# HDMI.net
KiCad netlist of a schematic drawn in Altium Designer
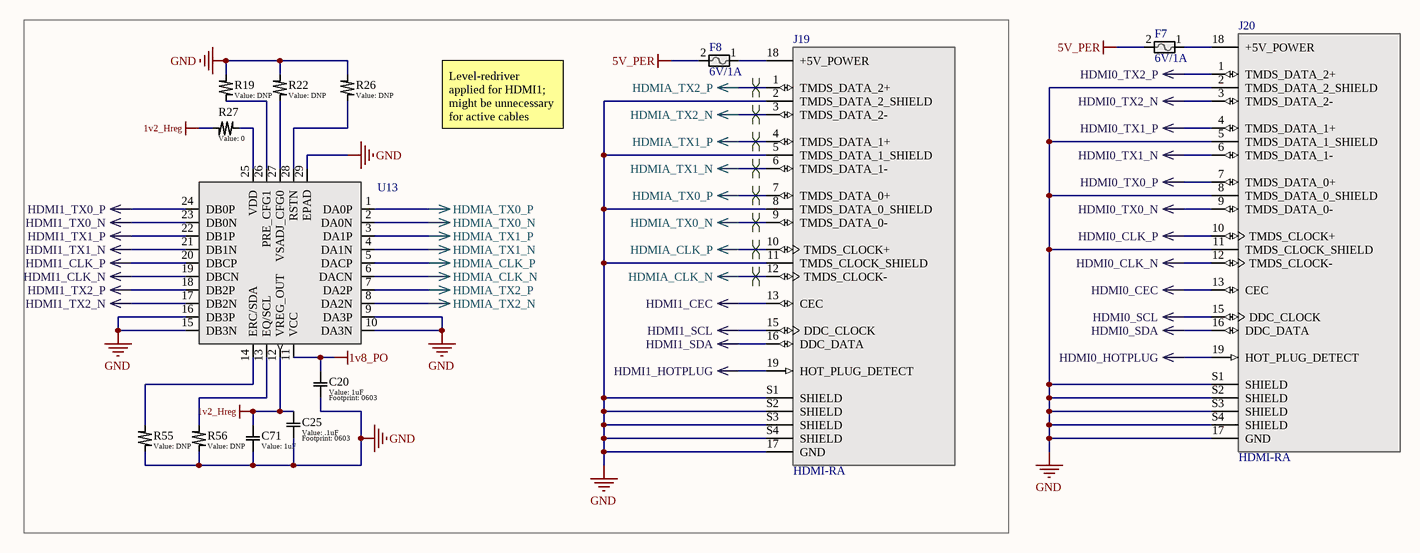
[diagram p0: HDMI.SchDoc]

(export (version "E")
  (design (tool "Eeschema 10.0.6"))
  (components
    (comp (ref "C20")
      (value "1uF")
      (footprint "0603")
      (fields
        (field (name "VOLTAGE") ">10V")
        (field (name "TOLERANCE") "10%")
        (field (name "Comment") "Generic Capacitor")
      )
      (libsource (lib "Capacitors") (part "Generic Capacitor"))
    )
    (comp (ref "C25")
      (value ".1uF")
      (footprint "0603")
      (fields
        (field (name "VOLTAGE") ">10V")
        (field (name "TOLERANCE") "10%")
        (field (name "Comment") "Generic Capacitor")
      )
      (libsource (lib "Capacitors") (part "Generic Capacitor"))
    )
    (comp (ref "C71")
      (value "1uF")
      (footprint "0603")
      (fields
        (field (name "VOLTAGE") ">10V")
        (field (name "TOLERANCE") "10%")
        (field (name "Comment") "Generic Capacitor")
      )
      (libsource (lib "Capacitors") (part "Generic Capacitor"))
    )
    (comp (ref "F7")
      (value "6V/1A")
      (footprint "0805")
      (description "Polymeric PTC Resettable Fuse 6V 1 A Ih Surface Mount 0805 (2012 Metric), Concave")
      (fields (field (name "MANUFACTURER") "Bel") (field (name "MANUFACTURER PART NUMBER") "0ZCK0100FF2E"))
      (libsource (lib "Regulators") (part "0ZCK0100FF2E"))
    )
    (comp (ref "F8")
      (value "6V/1A")
      (footprint "0805")
      (description "Polymeric PTC Resettable Fuse 6V 1 A Ih Surface Mount 0805 (2012 Metric), Concave")
      (fields (field (name "MANUFACTURER") "Bel") (field (name "MANUFACTURER PART NUMBER") "0ZCK0100FF2E"))
      (libsource (lib "Regulators") (part "0ZCK0100FF2E"))
    )
    (comp (ref "J19")
      (value "HDMI-RA")
      (footprint "CUI_HD01-19-RA-TH")
      (description "HDMI 2.1, Receptacle Connector, 19 Position, Through Hole, Vertical, Right Angle, Tray Packaging")
      (fields (field (name "MF") "CUI Devices") (field (name "DIGI-KEY_PART_NUMBER") "2223-HD01-19-RA-TH-ND"))
      (libsource (lib "Connectors") (part "HD01-19-RA-TH"))
    )
    (comp (ref "J20")
      (value "HDMI-RA")
      (footprint "CUI_HD01-19-RA-TH")
      (description "HDMI 2.1, Receptacle Connector, 19 Position, Through Hole, Vertical, Right Angle, Tray Packaging")
      (fields (field (name "MF") "CUI Devices") (field (name "DIGI-KEY_PART_NUMBER") "2223-HD01-19-RA-TH-ND"))
      (libsource (lib "Connectors") (part "HD01-19-RA-TH"))
    )
    (comp (ref "R19")
      (value "DNP")
      (footprint "0603")
      (fields
        (field (name "TOLERANCE") "1%")
        (field (name "POWER") "1/10W")
        (field (name "Comment") "Generic Resistor")
      )
      (libsource (lib "Resistors") (part "Generic Resistor"))
    )
    (comp (ref "R22")
      (value "DNP")
      (footprint "0603")
      (fields
        (field (name "TOLERANCE") "1%")
        (field (name "POWER") "1/10W")
        (field (name "Comment") "Generic Resistor")
      )
      (libsource (lib "Resistors") (part "Generic Resistor"))
    )
    (comp (ref "R26")
      (value "DNP")
      (footprint "0603")
      (fields
        (field (name "TOLERANCE") "1%")
        (field (name "POWER") "1/10W")
        (field (name "Comment") "Generic Resistor")
      )
      (libsource (lib "Resistors") (part "Generic Resistor"))
    )
    (comp (ref "R27")
      (value "0")
      (footprint "0603")
      (fields
        (field (name "TOLERANCE") "1%")
        (field (name "POWER") "1/10W")
        (field (name "Comment") "Generic Resistor")
      )
      (libsource (lib "Resistors") (part "Generic Resistor"))
    )
    (comp (ref "R55")
      (value "DNP")
      (footprint "0603")
      (fields
        (field (name "TOLERANCE") "1%")
        (field (name "POWER") "1/10W")
        (field (name "Comment") "Generic Resistor")
      )
      (libsource (lib "Resistors") (part "Generic Resistor"))
    )
    (comp (ref "R56")
      (value "DNP")
      (footprint "0603")
      (fields
        (field (name "TOLERANCE") "1%")
        (field (name "POWER") "1/10W")
        (field (name "Comment") "Generic Resistor")
      )
      (libsource (lib "Resistors") (part "Generic Resistor"))
    )
    (comp (ref "U13")
      (value "HDMI-Re")
      (footprint "28-WQFN (5.5x3.5)")
      (description "Video Retimer IC I2C 28-WQFN (5.5x3.5) Package")
      (libsource (lib "Misc ICs") (part "SN65DPHY440SSRHRR"))
    )
  )
  (nets
    (net (code "1") (name "1v2_Hreg") (class "Default")
      (node (ref "C25") (pin "1") (pinfunction "1_1") (pintype "passive"))
      (node (ref "C71") (pin "1") (pinfunction "1_1") (pintype "passive"))
      (node (ref "R27") (pin "1") (pinfunction "1_1") (pintype "passive"))
      (node (ref "U13") (pin "12") (pinfunction "VREG_OUT_12") (pintype "output"))
    )
    (net (code "2") (name "1v8_PO") (class "Default")
      (node (ref "C20") (pin "1") (pinfunction "1_1") (pintype "passive"))
      (node (ref "U13") (pin "11") (pinfunction "VCC_11") (pintype "power_in"))
    )
    (net (code "3") (name "5V_PER") (class "Default")
      (node (ref "F7") (pin "2") (pinfunction "2_2") (pintype "passive"))
      (node (ref "F8") (pin "2") (pinfunction "2_2") (pintype "passive"))
    )
    (net (code "4") (name "GND") (class "Default")
      (node (ref "C20") (pin "2") (pinfunction "2_2") (pintype "passive"))
      (node (ref "C25") (pin "2") (pinfunction "2_2") (pintype "passive"))
      (node (ref "C71") (pin "2") (pinfunction "2_2") (pintype "passive"))
      (node (ref "J19") (pin "11") (pinfunction "TMDS_CLOCK_SHIELD_11") (pintype "passive"))
      (node (ref "J19") (pin "17") (pinfunction "GND_17") (pintype "power_in"))
      (node (ref "J19") (pin "2") (pinfunction "TMDS_DATA_2_SHIELD_2") (pintype "passive"))
      (node (ref "J19") (pin "5") (pinfunction "TMDS_DATA_1_SHIELD_5") (pintype "passive"))
      (node (ref "J19") (pin "8") (pinfunction "TMDS_DATA_0_SHIELD_8") (pintype "passive"))
      (node (ref "J19") (pin "S1") (pinfunction "SHIELD_S1") (pintype "passive"))
      (node (ref "J19") (pin "S2") (pinfunction "SHIELD_S2") (pintype "passive"))
      (node (ref "J19") (pin "S3") (pinfunction "SHIELD_S3") (pintype "passive"))
      (node (ref "J19") (pin "S4") (pinfunction "SHIELD_S4") (pintype "passive"))
      (node (ref "J20") (pin "11") (pinfunction "TMDS_CLOCK_SHIELD_11") (pintype "passive"))
      (node (ref "J20") (pin "17") (pinfunction "GND_17") (pintype "power_in"))
      (node (ref "J20") (pin "2") (pinfunction "TMDS_DATA_2_SHIELD_2") (pintype "passive"))
      (node (ref "J20") (pin "5") (pinfunction "TMDS_DATA_1_SHIELD_5") (pintype "passive"))
      (node (ref "J20") (pin "8") (pinfunction "TMDS_DATA_0_SHIELD_8") (pintype "passive"))
      (node (ref "J20") (pin "S1") (pinfunction "SHIELD_S1") (pintype "passive"))
      (node (ref "J20") (pin "S2") (pinfunction "SHIELD_S2") (pintype "passive"))
      (node (ref "J20") (pin "S3") (pinfunction "SHIELD_S3") (pintype "passive"))
      (node (ref "J20") (pin "S4") (pinfunction "SHIELD_S4") (pintype "passive"))
      (node (ref "R19") (pin "2") (pinfunction "2_2") (pintype "passive"))
      (node (ref "R22") (pin "2") (pinfunction "2_2") (pintype "passive"))
      (node (ref "R26") (pin "2") (pinfunction "2_2") (pintype "passive"))
      (node (ref "R55") (pin "1") (pinfunction "1_1") (pintype "passive"))
      (node (ref "R56") (pin "1") (pinfunction "1_1") (pintype "passive"))
      (node (ref "U13") (pin "10") (pinfunction "DA3N_10") (pintype "bidirectional"))
      (node (ref "U13") (pin "15") (pinfunction "DB3N_15") (pintype "bidirectional"))
      (node (ref "U13") (pin "16") (pinfunction "DB3P_16") (pintype "bidirectional"))
      (node (ref "U13") (pin "29") (pinfunction "EPAD_29") (pintype "passive"))
      (node (ref "U13") (pin "9") (pinfunction "DA3P_9") (pintype "bidirectional"))
    )
    (net (code "5") (name "HDMI0_CEC") (class "Default")
      (node (ref "J20") (pin "13") (pinfunction "CEC_13") (pintype "bidirectional"))
    )
    (net (code "6") (name "HDMI0_CLK_N") (class "Default")
      (node (ref "J20") (pin "12") (pinfunction "TMDS_CLOCK-_12") (pintype "bidirectional"))
    )
    (net (code "7") (name "HDMI0_CLK_P") (class "Default")
      (node (ref "J20") (pin "10") (pinfunction "TMDS_CLOCK+_10") (pintype "bidirectional"))
    )
    (net (code "8") (name "HDMI0_HOTPLUG") (class "Default")
      (node (ref "J20") (pin "19") (pinfunction "HOT_PLUG_DETECT_19") (pintype "input"))
    )
    (net (code "9") (name "HDMI0_SCL") (class "Default")
      (node (ref "J20") (pin "15") (pinfunction "DDC_CLOCK_15") (pintype "bidirectional"))
    )
    (net (code "10") (name "HDMI0_SDA") (class "Default")
      (node (ref "J20") (pin "16") (pinfunction "DDC_DATA_16") (pintype "bidirectional"))
    )
    (net (code "11") (name "HDMI0_TX0_N") (class "Default")
      (node (ref "J20") (pin "9") (pinfunction "TMDS_DATA_0-_9") (pintype "bidirectional"))
    )
    (net (code "12") (name "HDMI0_TX0_P") (class "Default")
      (node (ref "J20") (pin "7") (pinfunction "TMDS_DATA_0+_7") (pintype "bidirectional"))
    )
    (net (code "13") (name "HDMI0_TX1_N") (class "Default")
      (node (ref "J20") (pin "6") (pinfunction "TMDS_DATA_1-_6") (pintype "bidirectional"))
    )
    (net (code "14") (name "HDMI0_TX1_P") (class "Default")
      (node (ref "J20") (pin "4") (pinfunction "TMDS_DATA_1+_4") (pintype "bidirectional"))
    )
    (net (code "15") (name "HDMI0_TX2_N") (class "Default")
      (node (ref "J20") (pin "3") (pinfunction "TMDS_DATA_2-_3") (pintype "bidirectional"))
    )
    (net (code "16") (name "HDMI0_TX2_P") (class "Default")
      (node (ref "J20") (pin "1") (pinfunction "TMDS_DATA_2+_1") (pintype "bidirectional"))
    )
    (net (code "17") (name "HDMI1_CEC") (class "Default")
      (node (ref "J19") (pin "13") (pinfunction "CEC_13") (pintype "bidirectional"))
    )
    (net (code "18") (name "HDMI1_CLK_N") (class "Default")
      (node (ref "U13") (pin "19") (pinfunction "DBCN_19") (pintype "passive"))
    )
    (net (code "19") (name "HDMI1_CLK_P") (class "Default")
      (node (ref "U13") (pin "20") (pinfunction "DBCP_20") (pintype "passive"))
    )
    (net (code "20") (name "HDMI1_HOTPLUG") (class "Default")
      (node (ref "J19") (pin "19") (pinfunction "HOT_PLUG_DETECT_19") (pintype "input"))
    )
    (net (code "21") (name "HDMI1_SCL") (class "Default")
      (node (ref "J19") (pin "15") (pinfunction "DDC_CLOCK_15") (pintype "bidirectional"))
    )
    (net (code "22") (name "HDMI1_SDA") (class "Default")
      (node (ref "J19") (pin "16") (pinfunction "DDC_DATA_16") (pintype "bidirectional"))
    )
    (net (code "23") (name "HDMI1_TX0_N") (class "Default")
      (node (ref "U13") (pin "23") (pinfunction "DB0N_23") (pintype "bidirectional"))
    )
    (net (code "24") (name "HDMI1_TX0_P") (class "Default")
      (node (ref "U13") (pin "24") (pinfunction "DB0P_24") (pintype "bidirectional"))
    )
    (net (code "25") (name "HDMI1_TX1_N") (class "Default")
      (node (ref "U13") (pin "21") (pinfunction "DB1N_21") (pintype "bidirectional"))
    )
    (net (code "26") (name "HDMI1_TX1_P") (class "Default")
      (node (ref "U13") (pin "22") (pinfunction "DB1P_22") (pintype "bidirectional"))
    )
    (net (code "27") (name "HDMI1_TX2_N") (class "Default")
      (node (ref "U13") (pin "17") (pinfunction "DB2N_17") (pintype "bidirectional"))
    )
    (net (code "28") (name "HDMI1_TX2_P") (class "Default")
      (node (ref "U13") (pin "18") (pinfunction "DB2P_18") (pintype "bidirectional"))
    )
    (net (code "29") (name "HDMIA_CLK_N") (class "Default")
      (node (ref "J19") (pin "12") (pinfunction "TMDS_CLOCK-_12") (pintype "bidirectional"))
      (node (ref "U13") (pin "6") (pinfunction "DACN_6") (pintype "passive"))
    )
    (net (code "30") (name "HDMIA_CLK_P") (class "Default")
      (node (ref "J19") (pin "10") (pinfunction "TMDS_CLOCK+_10") (pintype "bidirectional"))
      (node (ref "U13") (pin "5") (pinfunction "DACP_5") (pintype "passive"))
    )
    (net (code "31") (name "HDMIA_TX0_N") (class "Default")
      (node (ref "J19") (pin "9") (pinfunction "TMDS_DATA_0-_9") (pintype "bidirectional"))
      (node (ref "U13") (pin "2") (pinfunction "DA0N_2") (pintype "bidirectional"))
    )
    (net (code "32") (name "HDMIA_TX0_P") (class "Default")
      (node (ref "J19") (pin "7") (pinfunction "TMDS_DATA_0+_7") (pintype "bidirectional"))
      (node (ref "U13") (pin "1") (pinfunction "DA0P_1") (pintype "bidirectional"))
    )
    (net (code "33") (name "HDMIA_TX1_N") (class "Default")
      (node (ref "J19") (pin "6") (pinfunction "TMDS_DATA_1-_6") (pintype "bidirectional"))
      (node (ref "U13") (pin "4") (pinfunction "DA1N_4") (pintype "bidirectional"))
    )
    (net (code "34") (name "HDMIA_TX1_P") (class "Default")
      (node (ref "J19") (pin "4") (pinfunction "TMDS_DATA_1+_4") (pintype "bidirectional"))
      (node (ref "U13") (pin "3") (pinfunction "DA1P_3") (pintype "bidirectional"))
    )
    (net (code "35") (name "HDMIA_TX2_N") (class "Default")
      (node (ref "J19") (pin "3") (pinfunction "TMDS_DATA_2-_3") (pintype "bidirectional"))
      (node (ref "U13") (pin "8") (pinfunction "DA2N_8") (pintype "bidirectional"))
    )
    (net (code "36") (name "HDMIA_TX2_P") (class "Default")
      (node (ref "J19") (pin "1") (pinfunction "TMDS_DATA_2+_1") (pintype "bidirectional"))
      (node (ref "U13") (pin "7") (pinfunction "DA2P_7") (pintype "bidirectional"))
    )
    (net (code "37") (name "Net-(J19-+5V_POWER)") (class "Default")
      (node (ref "F8") (pin "1") (pinfunction "1_1") (pintype "passive"))
      (node (ref "J19") (pin "18") (pinfunction "+5V_POWER_18") (pintype "power_in"))
    )
    (net (code "38") (name "Net-(J20-+5V_POWER)") (class "Default")
      (node (ref "F7") (pin "1") (pinfunction "1_1") (pintype "passive"))
      (node (ref "J20") (pin "18") (pinfunction "+5V_POWER_18") (pintype "power_in"))
    )
    (net (code "39") (name "Net-(U13-EQ{slash}SCL)") (class "Default")
      (node (ref "R56") (pin "2") (pinfunction "2_2") (pintype "passive"))
      (node (ref "U13") (pin "13") (pinfunction "EQ/SCL_13") (pintype "passive"))
    )
    (net (code "40") (name "Net-(U13-ERC{slash}SDA)") (class "Default")
      (node (ref "R55") (pin "2") (pinfunction "2_2") (pintype "passive"))
      (node (ref "U13") (pin "14") (pinfunction "ERC/SDA_14") (pintype "passive"))
    )
    (net (code "41") (name "Net-(U13-PRE_CFG1)") (class "Default")
      (node (ref "R19") (pin "1") (pinfunction "1_1") (pintype "passive"))
      (node (ref "U13") (pin "26") (pinfunction "PRE_CFG1_26") (pintype "passive"))
    )
    (net (code "42") (name "Net-(U13-RSTN)") (class "Default")
      (node (ref "R26") (pin "1") (pinfunction "1_1") (pintype "passive"))
      (node (ref "U13") (pin "28") (pinfunction "RSTN_28") (pintype "passive"))
    )
    (net (code "43") (name "Net-(U13-VDD)") (class "Default")
      (node (ref "R27") (pin "2") (pinfunction "2_2") (pintype "passive"))
      (node (ref "U13") (pin "25") (pinfunction "VDD_25") (pintype "power_in"))
    )
    (net (code "44") (name "Net-(U13-VSADJ_CFG0)") (class "Default")
      (node (ref "R22") (pin "1") (pinfunction "1_1") (pintype "passive"))
      (node (ref "U13") (pin "27") (pinfunction "VSADJ_CFG0_27") (pintype "passive"))
    )
  )
)
